# Feather_j-link.net
KiCad netlist of a schematic drawn in EAGLE
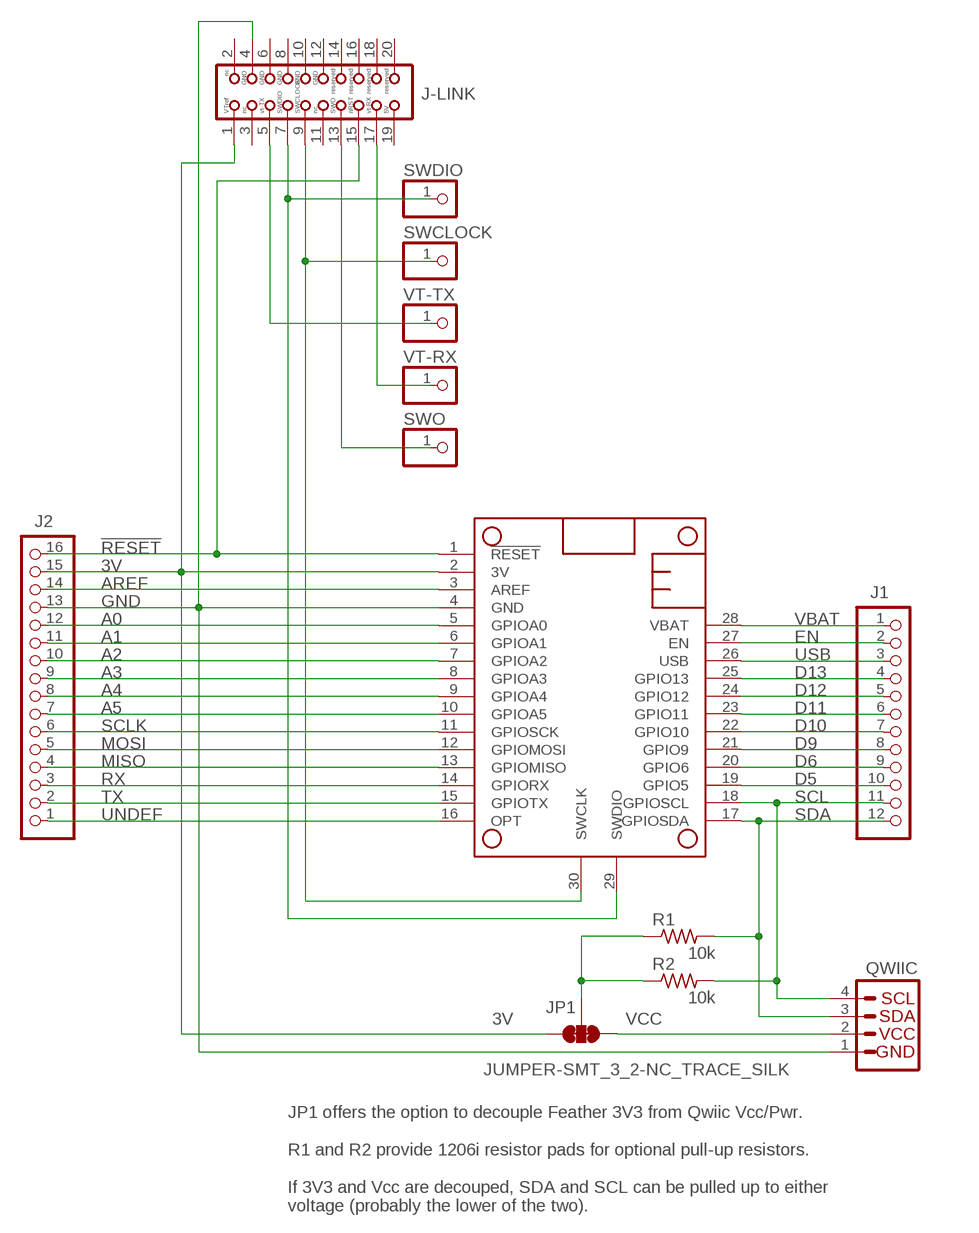
[diagram p0: schematic, sheet 1]

(export (version "E")
  (design (tool "Eeschema 10.0.6"))
  (components
    (comp (ref "J-LINK")
      (value "JLINK-ARM")
      (footprint "eagle-import:JTAG-ARM")
      (libsource (lib "eagle-import") (part "JLINK-ARM"))
    )
    (comp (ref "J1")
      (value "HEADER-1X1276MIL")
      (footprint "eagle-import:1X12_ROUND_76MIL")
      (libsource (lib "eagle-import") (part "HEADER-1X1276MIL"))
    )
    (comp (ref "J2")
      (value "HEADER-1X16ROUND")
      (footprint "eagle-import:1X16_ROUND")
      (libsource (lib "eagle-import") (part "HEADER-1X16ROUND"))
    )
    (comp (ref "JP1")
      (value "JUMPER-SMT_3_2-NC_TRACE_SILK")
      (footprint "eagle-import:SMT-JUMPER_3_2-NC_TRACE_SILK")
      (libsource (lib "eagle-import") (part "JUMPER-SMT_3_2-NC_TRACE_SILK"))
    )
    (comp (ref "MS2")
      (value "FEATHERWING-SWD-SWD")
      (footprint "eagle-import:FEATHERWING_DIM_SWD")
      (libsource (lib "eagle-import") (part "FEATHERWING-SWD-SWD"))
    )
    (comp (ref "QWIIC")
      (value "QWIIC_CONNECTORJS-1MM")
      (footprint "eagle-import:1X04_1MM_RA")
      (libsource (lib "eagle-import") (part "QWIIC_CONNECTORJS-1MM"))
    )
    (comp (ref "R1")
      (value "10k")
      (footprint "eagle-import:M1206")
      (libsource (lib "eagle-import") (part "R-US_M1206"))
    )
    (comp (ref "R2")
      (value "10k")
      (footprint "eagle-import:M1206")
      (libsource (lib "eagle-import") (part "R-US_M1206"))
    )
    (comp (ref "SWCLOCK")
      (value "PINHD-1X1")
      (footprint "eagle-import:1X01")
      (libsource (lib "eagle-import") (part "PINHD-1X1"))
    )
    (comp (ref "SWDIO")
      (value "PINHD-1X1")
      (footprint "eagle-import:1X01")
      (libsource (lib "eagle-import") (part "PINHD-1X1"))
    )
    (comp (ref "SWO")
      (value "PINHD-1X1")
      (footprint "eagle-import:1X01")
      (libsource (lib "eagle-import") (part "PINHD-1X1"))
    )
    (comp (ref "VT-RX")
      (value "PINHD-1X1")
      (footprint "eagle-import:1X01")
      (libsource (lib "eagle-import") (part "PINHD-1X1"))
    )
    (comp (ref "VT-TX")
      (value "PINHD-1X1")
      (footprint "eagle-import:1X01")
      (libsource (lib "eagle-import") (part "PINHD-1X1"))
    )
  )
  (nets
    (net (code "1") (name "/3V") (class "Default")
      (node (ref "J-LINK") (pin "1") (pinfunction "1_1") (pintype "passive"))
      (node (ref "J2") (pin "15") (pinfunction "15_15") (pintype "passive"))
      (node (ref "JP1") (pin "3") (pinfunction "3_3") (pintype "passive"))
      (node (ref "MS2") (pin "2") (pinfunction "3V_2") (pintype "power_in"))
    )
    (net (code "2") (name "/A0") (class "Default")
      (node (ref "J2") (pin "12") (pinfunction "12_12") (pintype "passive"))
      (node (ref "MS2") (pin "5") (pinfunction "GPIOA0_5") (pintype "bidirectional"))
    )
    (net (code "3") (name "/A1") (class "Default")
      (node (ref "J2") (pin "11") (pinfunction "11_11") (pintype "passive"))
      (node (ref "MS2") (pin "6") (pinfunction "GPIOA1_6") (pintype "bidirectional"))
    )
    (net (code "4") (name "/A2") (class "Default")
      (node (ref "J2") (pin "10") (pinfunction "10_10") (pintype "passive"))
      (node (ref "MS2") (pin "7") (pinfunction "GPIOA2_7") (pintype "bidirectional"))
    )
    (net (code "5") (name "/A3") (class "Default")
      (node (ref "J2") (pin "9") (pinfunction "9_9") (pintype "passive"))
      (node (ref "MS2") (pin "8") (pinfunction "GPIOA3_8") (pintype "bidirectional"))
    )
    (net (code "6") (name "/A4") (class "Default")
      (node (ref "J2") (pin "8") (pinfunction "8_8") (pintype "passive"))
      (node (ref "MS2") (pin "9") (pinfunction "GPIOA4_9") (pintype "bidirectional"))
    )
    (net (code "7") (name "/A5") (class "Default")
      (node (ref "J2") (pin "7") (pinfunction "7_7") (pintype "passive"))
      (node (ref "MS2") (pin "10") (pinfunction "GPIOA5_10") (pintype "bidirectional"))
    )
    (net (code "8") (name "/AREF") (class "Default")
      (node (ref "J2") (pin "14") (pinfunction "14_14") (pintype "passive"))
      (node (ref "MS2") (pin "3") (pinfunction "AREF_3") (pintype "passive"))
    )
    (net (code "9") (name "/D5") (class "Default")
      (node (ref "J1") (pin "10") (pinfunction "10_10") (pintype "passive"))
      (node (ref "MS2") (pin "19") (pinfunction "GPIO5_19") (pintype "bidirectional"))
    )
    (net (code "10") (name "/D6") (class "Default")
      (node (ref "J1") (pin "9") (pinfunction "9_9") (pintype "passive"))
      (node (ref "MS2") (pin "20") (pinfunction "GPIO6_20") (pintype "bidirectional"))
    )
    (net (code "11") (name "/D9") (class "Default")
      (node (ref "J1") (pin "8") (pinfunction "8_8") (pintype "passive"))
      (node (ref "MS2") (pin "21") (pinfunction "GPIO9_21") (pintype "bidirectional"))
    )
    (net (code "12") (name "/D10") (class "Default")
      (node (ref "J1") (pin "7") (pinfunction "7_7") (pintype "passive"))
      (node (ref "MS2") (pin "22") (pinfunction "GPIO10_22") (pintype "bidirectional"))
    )
    (net (code "13") (name "/D11") (class "Default")
      (node (ref "J1") (pin "6") (pinfunction "6_6") (pintype "passive"))
      (node (ref "MS2") (pin "23") (pinfunction "GPIO11_23") (pintype "bidirectional"))
    )
    (net (code "14") (name "/D12") (class "Default")
      (node (ref "J1") (pin "5") (pinfunction "5_5") (pintype "passive"))
      (node (ref "MS2") (pin "24") (pinfunction "GPIO12_24") (pintype "bidirectional"))
    )
    (net (code "15") (name "/D13") (class "Default")
      (node (ref "J1") (pin "4") (pinfunction "4_4") (pintype "passive"))
      (node (ref "MS2") (pin "25") (pinfunction "GPIO13_25") (pintype "bidirectional"))
    )
    (net (code "16") (name "/EN") (class "Default")
      (node (ref "J1") (pin "2") (pinfunction "2_2") (pintype "passive"))
      (node (ref "MS2") (pin "27") (pinfunction "EN_27") (pintype "passive"))
    )
    (net (code "17") (name "/GND") (class "Default")
      (node (ref "J-LINK") (pin "4") (pinfunction "4_4") (pintype "passive"))
      (node (ref "J2") (pin "13") (pinfunction "13_13") (pintype "passive"))
      (node (ref "MS2") (pin "4") (pinfunction "GND_4") (pintype "power_in"))
      (node (ref "QWIIC") (pin "1") (pinfunction "GND_1") (pintype "power_in"))
    )
    (net (code "18") (name "/MISO") (class "Default")
      (node (ref "J2") (pin "4") (pinfunction "4_4") (pintype "passive"))
      (node (ref "MS2") (pin "13") (pinfunction "GPIOMISO_13") (pintype "bidirectional"))
    )
    (net (code "19") (name "/MOSI") (class "Default")
      (node (ref "J2") (pin "5") (pinfunction "5_5") (pintype "passive"))
      (node (ref "MS2") (pin "12") (pinfunction "GPIOMOSI_12") (pintype "bidirectional"))
    )
    (net (code "20") (name "/RX") (class "Default")
      (node (ref "J2") (pin "3") (pinfunction "3_3") (pintype "passive"))
      (node (ref "MS2") (pin "14") (pinfunction "GPIORX_14") (pintype "bidirectional"))
    )
    (net (code "21") (name "/SCL") (class "Default")
      (node (ref "J1") (pin "11") (pinfunction "11_11") (pintype "passive"))
      (node (ref "MS2") (pin "18") (pinfunction "GPIOSCL_18") (pintype "bidirectional"))
      (node (ref "QWIIC") (pin "4") (pinfunction "SCL_4") (pintype "passive"))
      (node (ref "R2") (pin "2") (pinfunction "2_2") (pintype "passive"))
    )
    (net (code "22") (name "/SCLK") (class "Default")
      (node (ref "J2") (pin "6") (pinfunction "6_6") (pintype "passive"))
      (node (ref "MS2") (pin "11") (pinfunction "GPIOSCK_11") (pintype "bidirectional"))
    )
    (net (code "23") (name "/SDA") (class "Default")
      (node (ref "J1") (pin "12") (pinfunction "12_12") (pintype "passive"))
      (node (ref "MS2") (pin "17") (pinfunction "GPIOSDA_17") (pintype "bidirectional"))
      (node (ref "QWIIC") (pin "3") (pinfunction "SDA_3") (pintype "passive"))
      (node (ref "R1") (pin "2") (pinfunction "2_2") (pintype "passive"))
    )
    (net (code "24") (name "/TX") (class "Default")
      (node (ref "J2") (pin "2") (pinfunction "2_2") (pintype "passive"))
      (node (ref "MS2") (pin "15") (pinfunction "GPIOTX_15") (pintype "bidirectional"))
    )
    (net (code "25") (name "/UNDEF") (class "Default")
      (node (ref "J2") (pin "1") (pinfunction "1_1") (pintype "passive"))
      (node (ref "MS2") (pin "16") (pinfunction "OPT_16") (pintype "passive"))
    )
    (net (code "26") (name "/USB") (class "Default")
      (node (ref "J1") (pin "3") (pinfunction "3_3") (pintype "passive"))
      (node (ref "MS2") (pin "26") (pinfunction "USB_26") (pintype "power_in"))
    )
    (net (code "27") (name "/VBAT") (class "Default")
      (node (ref "J1") (pin "1") (pinfunction "1_1") (pintype "passive"))
      (node (ref "MS2") (pin "28") (pinfunction "VBAT_28") (pintype "power_in"))
    )
    (net (code "28") (name "/VCC") (class "Default")
      (node (ref "JP1") (pin "1") (pinfunction "1_1") (pintype "passive"))
      (node (ref "QWIIC") (pin "2") (pinfunction "VCC_2") (pintype "power_in"))
    )
    (net (code "29") (name "/~{RESET}") (class "Default")
      (node (ref "J-LINK") (pin "15") (pinfunction "15_15") (pintype "passive"))
      (node (ref "J2") (pin "16") (pinfunction "16_16") (pintype "passive"))
      (node (ref "MS2") (pin "1") (pinfunction "~{RESET}_1") (pintype "input"))
    )
    (net (code "30") (name "Net-(J-LINK-Pad5)") (class "Default")
      (node (ref "J-LINK") (pin "5") (pinfunction "5_5") (pintype "passive"))
      (node (ref "VT-TX") (pin "1") (pinfunction "1_1") (pintype "passive"))
    )
    (net (code "31") (name "Net-(J-LINK-Pad13)") (class "Default")
      (node (ref "J-LINK") (pin "13") (pinfunction "13_13") (pintype "passive"))
      (node (ref "SWO") (pin "1") (pinfunction "1_1") (pintype "passive"))
    )
    (net (code "32") (name "Net-(J-LINK-Pad17)") (class "Default")
      (node (ref "J-LINK") (pin "17") (pinfunction "17_17") (pintype "passive"))
      (node (ref "VT-RX") (pin "1") (pinfunction "1_1") (pintype "passive"))
    )
    (net (code "33") (name "Net-(JP1-Pad2)") (class "Default")
      (node (ref "JP1") (pin "2") (pinfunction "2_2") (pintype "passive"))
      (node (ref "R1") (pin "1") (pinfunction "1_1") (pintype "passive"))
      (node (ref "R2") (pin "1") (pinfunction "1_1") (pintype "passive"))
    )
    (net (code "34") (name "Net-(MS2-SWCLK)") (class "Default")
      (node (ref "J-LINK") (pin "9") (pinfunction "9_9") (pintype "passive"))
      (node (ref "MS2") (pin "30") (pinfunction "SWCLK_30") (pintype "bidirectional"))
      (node (ref "SWCLOCK") (pin "1") (pinfunction "1_1") (pintype "passive"))
    )
    (net (code "35") (name "Net-(MS2-SWDIO)") (class "Default")
      (node (ref "J-LINK") (pin "7") (pinfunction "7_7") (pintype "passive"))
      (node (ref "MS2") (pin "29") (pinfunction "SWDIO_29") (pintype "bidirectional"))
      (node (ref "SWDIO") (pin "1") (pinfunction "1_1") (pintype "passive"))
    )
    (net (code "36") (name "unconnected-(J-LINK-Pad2)") (class "Default")
      (node (ref "J-LINK") (pin "2") (pinfunction "2_2") (pintype "passive"))
    )
    (net (code "37") (name "unconnected-(J-LINK-Pad3)") (class "Default")
      (node (ref "J-LINK") (pin "3") (pinfunction "3_3") (pintype "passive"))
    )
    (net (code "38") (name "unconnected-(J-LINK-Pad6)") (class "Default")
      (node (ref "J-LINK") (pin "6") (pinfunction "6_6") (pintype "passive"))
    )
    (net (code "39") (name "unconnected-(J-LINK-Pad8)") (class "Default")
      (node (ref "J-LINK") (pin "8") (pinfunction "8_8") (pintype "passive"))
    )
    (net (code "40") (name "unconnected-(J-LINK-Pad10)") (class "Default")
      (node (ref "J-LINK") (pin "10") (pinfunction "10_10") (pintype "passive"))
    )
    (net (code "41") (name "unconnected-(J-LINK-Pad11)") (class "Default")
      (node (ref "J-LINK") (pin "11") (pinfunction "11_11") (pintype "passive"))
    )
    (net (code "42") (name "unconnected-(J-LINK-Pad12)") (class "Default")
      (node (ref "J-LINK") (pin "12") (pinfunction "12_12") (pintype "passive"))
    )
    (net (code "43") (name "unconnected-(J-LINK-Pad14)") (class "Default")
      (node (ref "J-LINK") (pin "14") (pinfunction "14_14") (pintype "passive"))
    )
    (net (code "44") (name "unconnected-(J-LINK-Pad16)") (class "Default")
      (node (ref "J-LINK") (pin "16") (pinfunction "16_16") (pintype "passive"))
    )
    (net (code "45") (name "unconnected-(J-LINK-Pad18)") (class "Default")
      (node (ref "J-LINK") (pin "18") (pinfunction "18_18") (pintype "passive"))
    )
    (net (code "46") (name "unconnected-(J-LINK-Pad19)") (class "Default")
      (node (ref "J-LINK") (pin "19") (pinfunction "19_19") (pintype "passive"))
    )
    (net (code "47") (name "unconnected-(J-LINK-Pad20)") (class "Default")
      (node (ref "J-LINK") (pin "20") (pinfunction "20_20") (pintype "passive"))
    )
  )
)
